# untitled.net
KiCad netlist of a schematic drawn in EAGLE
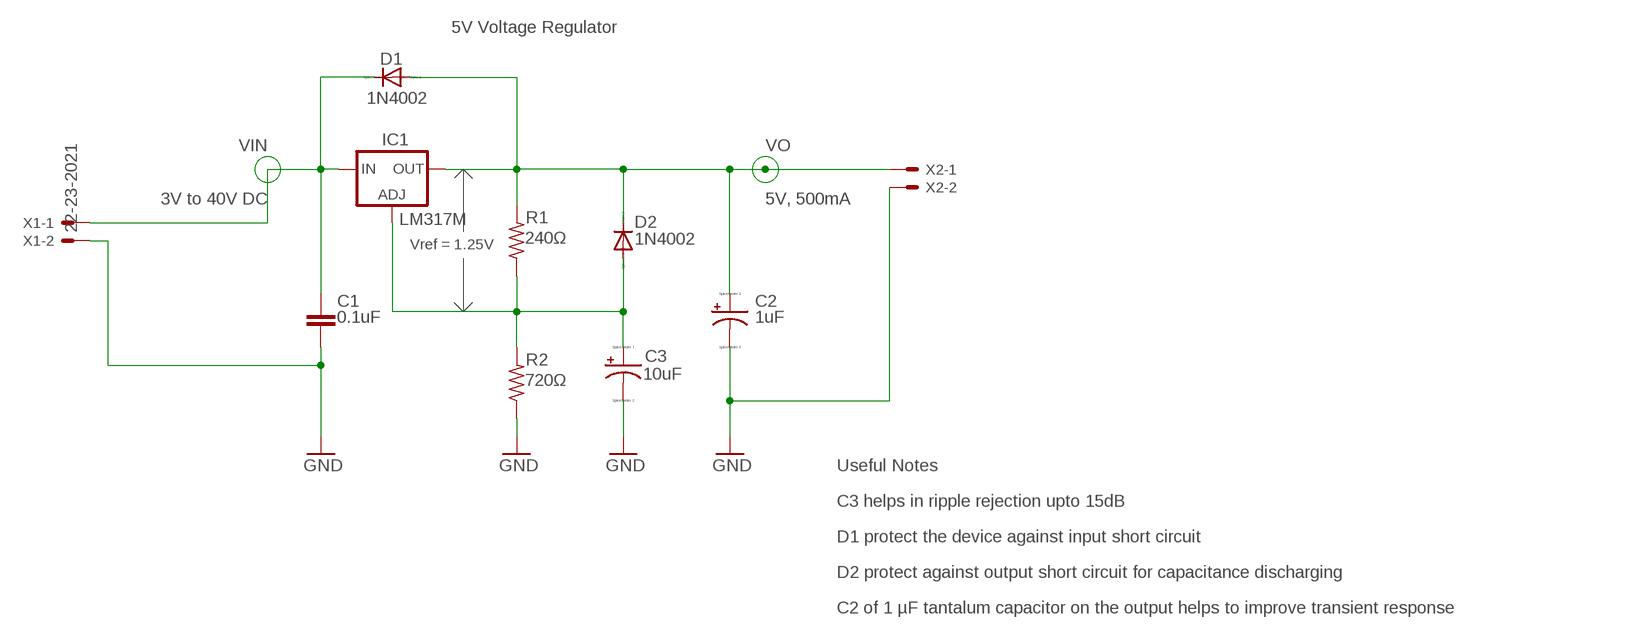
[diagram p0: schematic, sheet 1]

(export (version "E")
  (design (tool "Eeschema 10.0.6"))
  (components
    (comp (ref "C1")
      (value "0.1uF")
      (footprint "eagle-import:C075-052X106")
      (libsource (lib "eagle-import") (part "C-EU075-052X106"))
    )
    (comp (ref "C2")
      (value "1uF")
      (footprint "eagle-import:085CS_1AR")
      (libsource (lib "eagle-import") (part "CPOL-US085CS-1AR"))
    )
    (comp (ref "C3")
      (value "10uF")
      (footprint "eagle-import:085CS_1AR")
      (libsource (lib "eagle-import") (part "CPOL-US085CS-1AR"))
    )
    (comp (ref "D1")
      (value "1N4002")
      (footprint "eagle-import:DO41-10")
      (libsource (lib "eagle-import") (part "1N4004"))
    )
    (comp (ref "D2")
      (value "1N4002")
      (footprint "eagle-import:DO41-10")
      (libsource (lib "eagle-import") (part "1N4004"))
    )
    (comp (ref "IC1")
      (value "LM317MBSTT3")
      (footprint "eagle-import:SOT223")
      (fields (field (name "PARTNUMBER") "LM317M"))
      (libsource (lib "eagle-import") (part "LM317?MBSTT3"))
    )
    (comp (ref "R1")
      (value "240Ω")
      (footprint "eagle-import:M0805")
      (libsource (lib "eagle-import") (part "R-US_M0805"))
    )
    (comp (ref "R2")
      (value "720Ω")
      (footprint "eagle-import:M0805")
      (libsource (lib "eagle-import") (part "R-US_M0805"))
    )
    (comp (ref "X1")
      (value "22-23-2021")
      (footprint "eagle-import:22-23-2021")
      (fields (field (name "MF") "MOLEX"))
      (libsource (lib "eagle-import") (part "22-23-2021"))
    )
    (comp (ref "X2")
      (value "22-23-2021")
      (footprint "eagle-import:22-23-2021")
      (fields (field (name "MF") "MOLEX"))
      (libsource (lib "eagle-import") (part "22-23-2021"))
    )
  )
  (nets
    (net (code "1") (name "/VIN") (class "Default")
      (node (ref "C1") (pin "1") (pinfunction "1_1") (pintype "passive"))
      (node (ref "D1") (pin "C") (pinfunction "C_C") (pintype "passive"))
      (node (ref "IC1") (pin "3") (pinfunction "IN_3") (pintype "input"))
      (node (ref "X1") (pin "1") (pinfunction "S_1") (pintype "passive"))
    )
    (net (code "2") (name "/VO") (class "Default")
      (node (ref "C2") (pin "+") (pinfunction "+_+") (pintype "passive"))
      (node (ref "D1") (pin "A") (pinfunction "A_A") (pintype "passive"))
      (node (ref "D2") (pin "C") (pinfunction "C_C") (pintype "passive"))
      (node (ref "IC1") (pin "4") (pinfunction "OUT_4") (pintype "passive"))
      (node (ref "R1") (pin "2") (pinfunction "2_2") (pintype "passive"))
      (node (ref "X2") (pin "1") (pinfunction "S_1") (pintype "passive"))
    )
    (net (code "3") (name "GND") (class "Default")
      (node (ref "C1") (pin "2") (pinfunction "2_2") (pintype "passive"))
      (node (ref "C2") (pin "-") (pinfunction "-_-") (pintype "passive"))
      (node (ref "C3") (pin "-") (pinfunction "-_-") (pintype "passive"))
      (node (ref "R2") (pin "1") (pinfunction "1_1") (pintype "passive"))
      (node (ref "X1") (pin "2") (pinfunction "S_2") (pintype "passive"))
      (node (ref "X2") (pin "2") (pinfunction "S_2") (pintype "passive"))
    )
    (net (code "4") (name "Net-(IC1-ADJ)") (class "Default")
      (node (ref "C3") (pin "+") (pinfunction "+_+") (pintype "passive"))
      (node (ref "D2") (pin "A") (pinfunction "A_A") (pintype "passive"))
      (node (ref "IC1") (pin "1") (pinfunction "ADJ_1") (pintype "input"))
      (node (ref "R1") (pin "1") (pinfunction "1_1") (pintype "passive"))
      (node (ref "R2") (pin "2") (pinfunction "2_2") (pintype "passive"))
    )
  )
)
